# LED_board.net
KiCad netlist of a schematic drawn in EAGLE
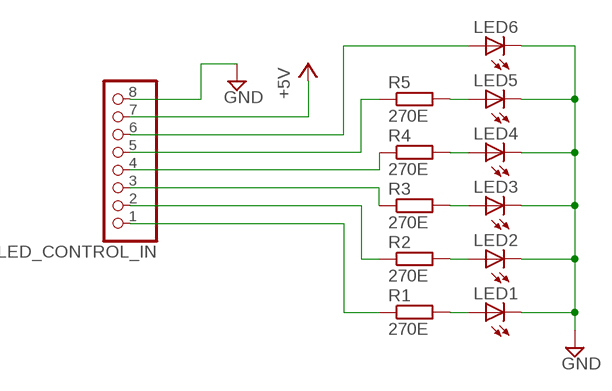
[diagram p0: schematic, sheet 1]

(export (version "E")
  (design (tool "Eeschema 10.0.6"))
  (components
    (comp (ref "LED1")
      (value "LED5MM")
      (footprint "eagle-import:LED5MM")
      (libsource (lib "eagle-import") (part "LED5MM"))
    )
    (comp (ref "LED2")
      (value "LED5MM")
      (footprint "eagle-import:LED5MM")
      (libsource (lib "eagle-import") (part "LED5MM"))
    )
    (comp (ref "LED3")
      (value "LED5MM")
      (footprint "eagle-import:LED5MM")
      (libsource (lib "eagle-import") (part "LED5MM"))
    )
    (comp (ref "LED4")
      (value "LED5MM")
      (footprint "eagle-import:LED5MM")
      (libsource (lib "eagle-import") (part "LED5MM"))
    )
    (comp (ref "LED5")
      (value "LED5MM")
      (footprint "eagle-import:LED5MM")
      (libsource (lib "eagle-import") (part "LED5MM"))
    )
    (comp (ref "LED6")
      (value "LED5MM")
      (footprint "eagle-import:LED5MM")
      (libsource (lib "eagle-import") (part "LED5MM"))
    )
    (comp (ref "LED_CONTROL_IN")
      (value "PINHD-1X8")
      (footprint "eagle-import:1X08")
      (libsource (lib "eagle-import") (part "PINHD-1X8"))
    )
    (comp (ref "R1")
      (value "270E")
      (footprint "eagle-import:R1206")
      (libsource (lib "eagle-import") (part "R-EU_R1206"))
    )
    (comp (ref "R2")
      (value "270E")
      (footprint "eagle-import:R1206")
      (libsource (lib "eagle-import") (part "R-EU_R1206"))
    )
    (comp (ref "R3")
      (value "270E")
      (footprint "eagle-import:R1206")
      (libsource (lib "eagle-import") (part "R-EU_R1206"))
    )
    (comp (ref "R4")
      (value "270E")
      (footprint "eagle-import:R1206")
      (libsource (lib "eagle-import") (part "R-EU_R1206"))
    )
    (comp (ref "R5")
      (value "270E")
      (footprint "eagle-import:R1206")
      (libsource (lib "eagle-import") (part "R-EU_R1206"))
    )
  )
  (nets
    (net (code "1") (name "+5V") (class "Default")
      (node (ref "LED_CONTROL_IN") (pin "7") (pinfunction "7_7") (pintype "passive"))
    )
    (net (code "2") (name "GND") (class "Default")
      (node (ref "LED1") (pin "K") (pinfunction "C_K") (pintype "passive"))
      (node (ref "LED2") (pin "K") (pinfunction "C_K") (pintype "passive"))
      (node (ref "LED3") (pin "K") (pinfunction "C_K") (pintype "passive"))
      (node (ref "LED4") (pin "K") (pinfunction "C_K") (pintype "passive"))
      (node (ref "LED5") (pin "K") (pinfunction "C_K") (pintype "passive"))
      (node (ref "LED6") (pin "K") (pinfunction "C_K") (pintype "passive"))
      (node (ref "LED_CONTROL_IN") (pin "8") (pinfunction "8_8") (pintype "passive"))
    )
    (net (code "3") (name "Net-(LED1-PadA)") (class "Default")
      (node (ref "LED1") (pin "A") (pinfunction "A_A") (pintype "passive"))
      (node (ref "R1") (pin "2") (pinfunction "2_2") (pintype "passive"))
    )
    (net (code "4") (name "Net-(LED2-PadA)") (class "Default")
      (node (ref "LED2") (pin "A") (pinfunction "A_A") (pintype "passive"))
      (node (ref "R2") (pin "2") (pinfunction "2_2") (pintype "passive"))
    )
    (net (code "5") (name "Net-(LED3-PadA)") (class "Default")
      (node (ref "LED3") (pin "A") (pinfunction "A_A") (pintype "passive"))
      (node (ref "R3") (pin "2") (pinfunction "2_2") (pintype "passive"))
    )
    (net (code "6") (name "Net-(LED4-PadA)") (class "Default")
      (node (ref "LED4") (pin "A") (pinfunction "A_A") (pintype "passive"))
      (node (ref "R4") (pin "2") (pinfunction "2_2") (pintype "passive"))
    )
    (net (code "7") (name "Net-(LED5-PadA)") (class "Default")
      (node (ref "LED5") (pin "A") (pinfunction "A_A") (pintype "passive"))
      (node (ref "R5") (pin "2") (pinfunction "2_2") (pintype "passive"))
    )
    (net (code "8") (name "Net-(LED6-PadA)") (class "Default")
      (node (ref "LED6") (pin "A") (pinfunction "A_A") (pintype "passive"))
      (node (ref "LED_CONTROL_IN") (pin "6") (pinfunction "6_6") (pintype "passive"))
    )
    (net (code "9") (name "Net-(LED_CONTROL_IN-Pad1)") (class "Default")
      (node (ref "LED_CONTROL_IN") (pin "1") (pinfunction "1_1") (pintype "passive"))
      (node (ref "R1") (pin "1") (pinfunction "1_1") (pintype "passive"))
    )
    (net (code "10") (name "Net-(LED_CONTROL_IN-Pad2)") (class "Default")
      (node (ref "LED_CONTROL_IN") (pin "2") (pinfunction "2_2") (pintype "passive"))
      (node (ref "R2") (pin "1") (pinfunction "1_1") (pintype "passive"))
    )
    (net (code "11") (name "Net-(LED_CONTROL_IN-Pad3)") (class "Default")
      (node (ref "LED_CONTROL_IN") (pin "3") (pinfunction "3_3") (pintype "passive"))
      (node (ref "R3") (pin "1") (pinfunction "1_1") (pintype "passive"))
    )
    (net (code "12") (name "Net-(LED_CONTROL_IN-Pad4)") (class "Default")
      (node (ref "LED_CONTROL_IN") (pin "4") (pinfunction "4_4") (pintype "passive"))
      (node (ref "R4") (pin "1") (pinfunction "1_1") (pintype "passive"))
    )
    (net (code "13") (name "Net-(LED_CONTROL_IN-Pad5)") (class "Default")
      (node (ref "LED_CONTROL_IN") (pin "5") (pinfunction "5_5") (pintype "passive"))
      (node (ref "R5") (pin "1") (pinfunction "1_1") (pintype "passive"))
    )
  )
)
